# SCH_Placa-TSM-2026-II_2026-04-09.net
KiCad netlist of a schematic drawn in EasyEDA
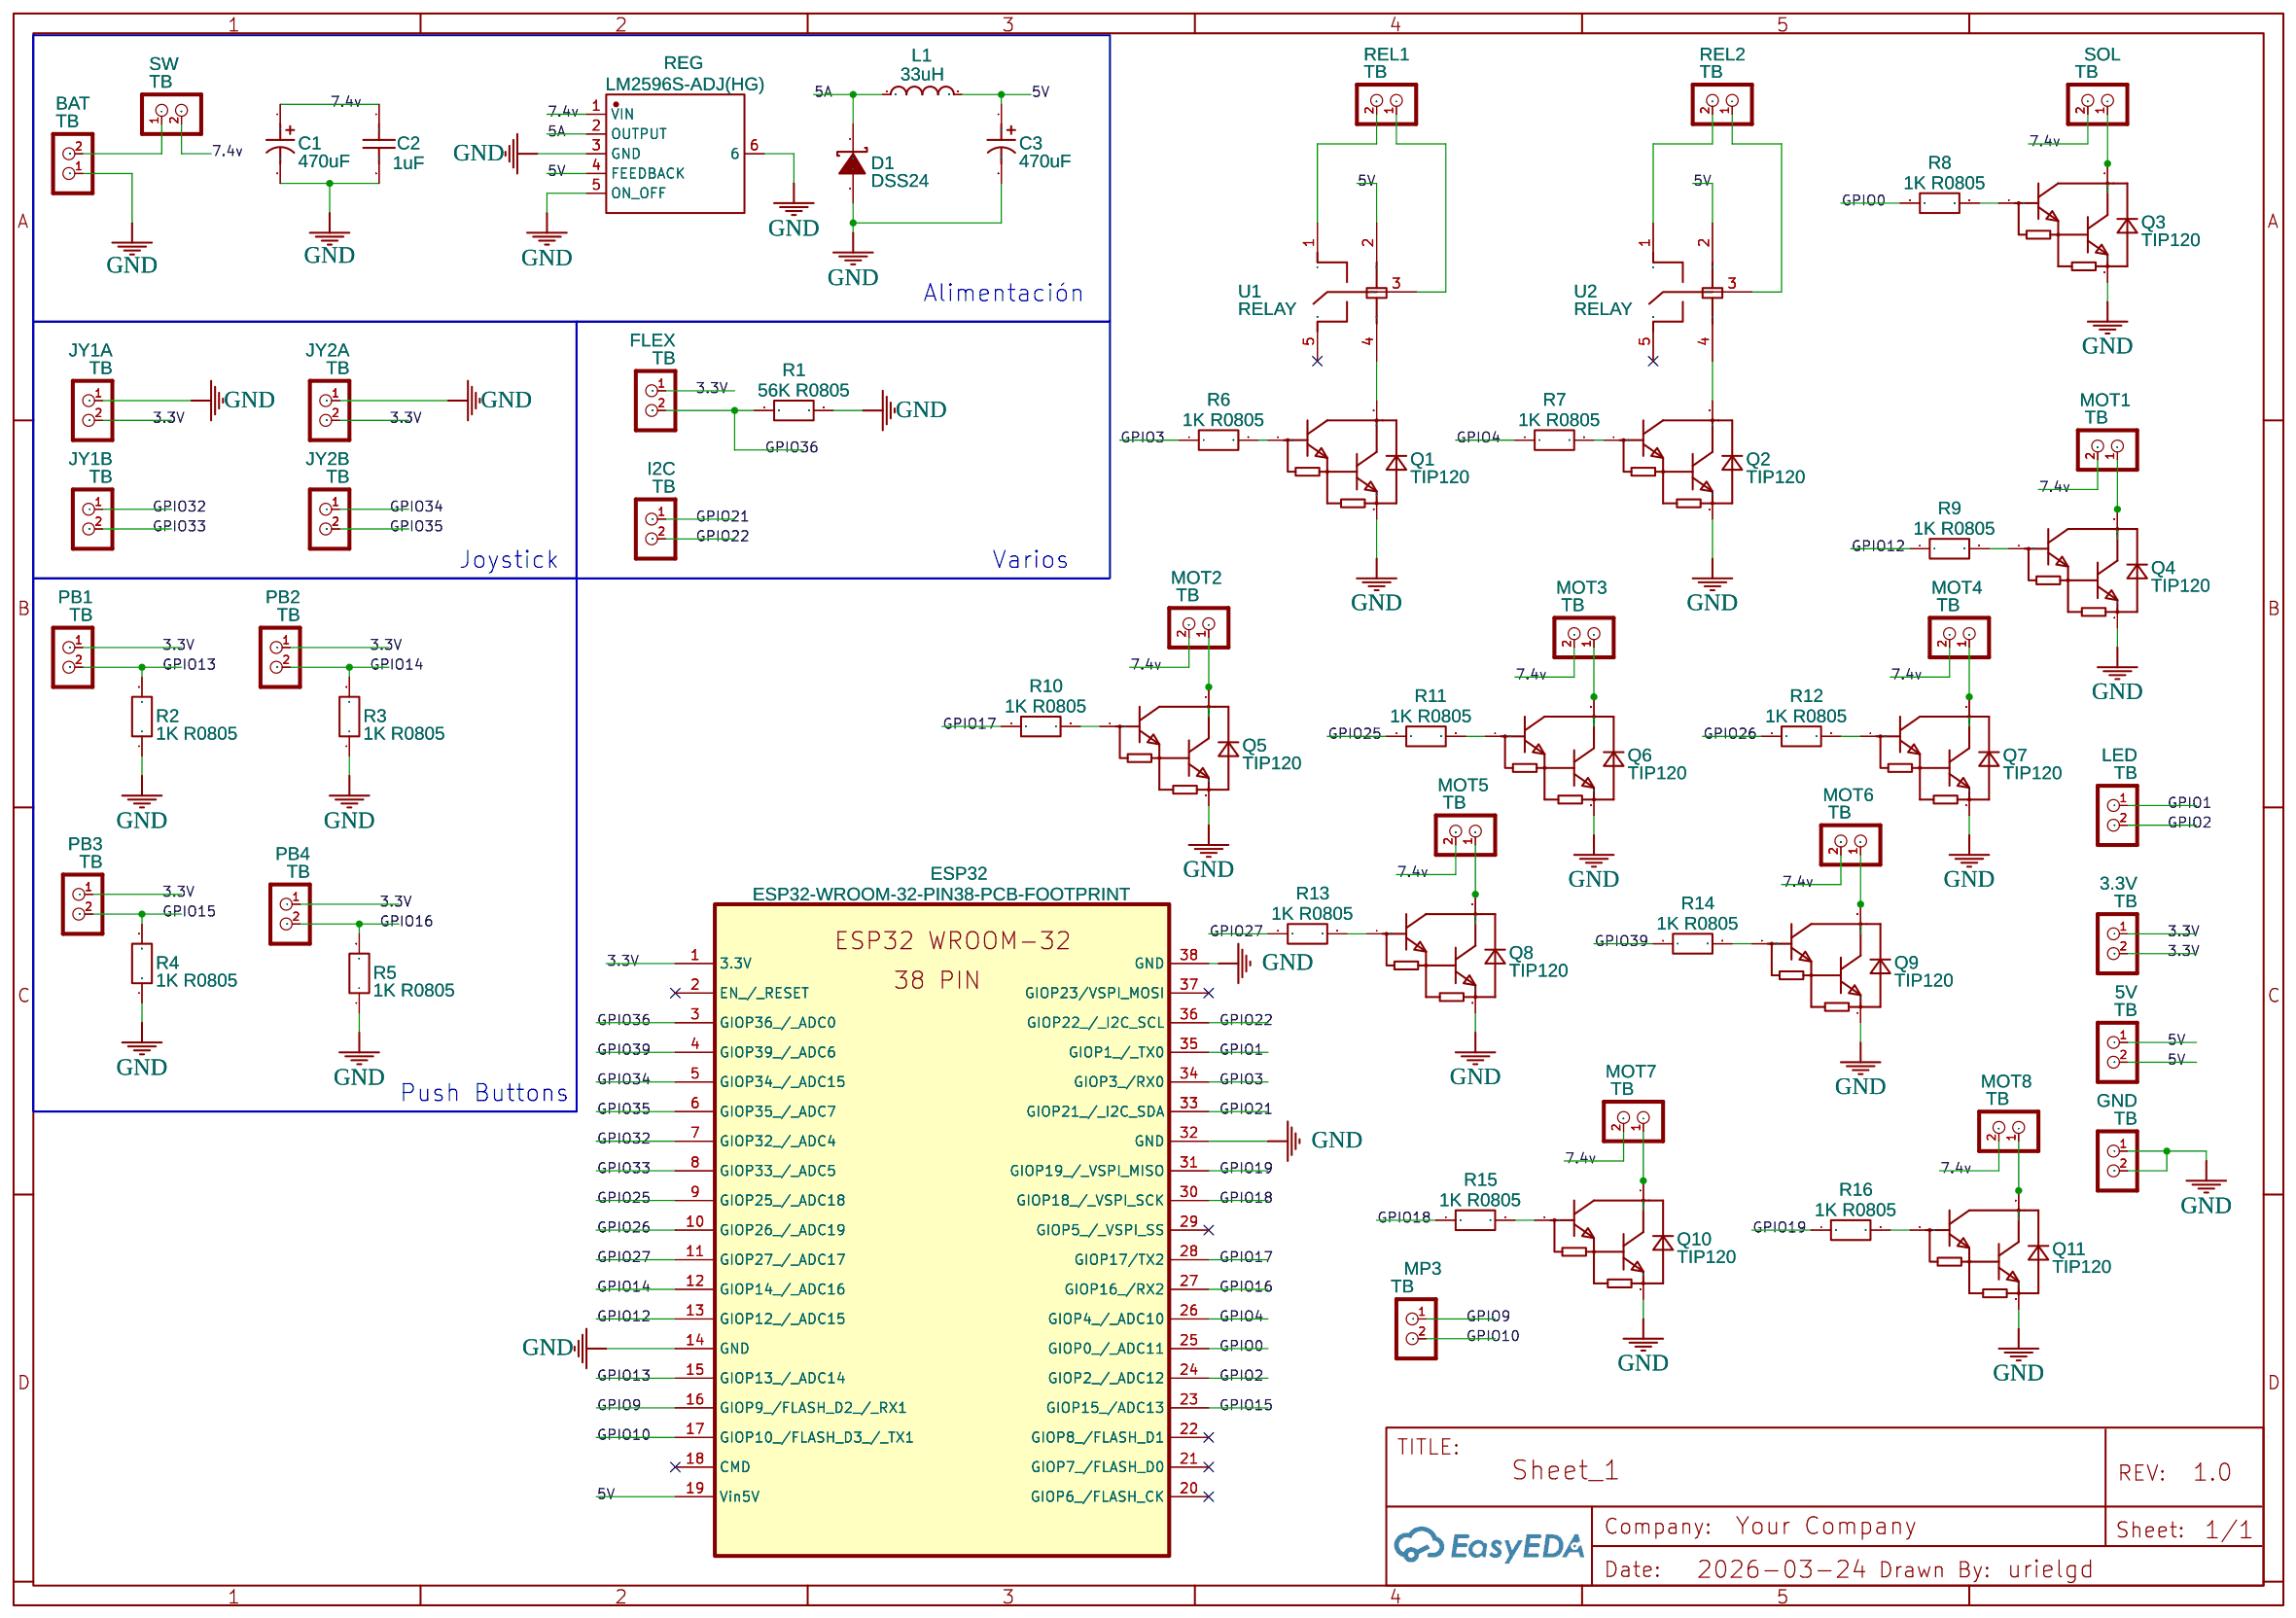
[diagram p0: schematic sheet]

(export (version "E")
  (design (tool "Eeschema 10.0.6"))
  (components
    (comp (ref "3.3V") (value "TB") (libsource (lib "") (part "TERMINAL_BLOCK_2P_5_14")))
    (comp (ref "5V") (value "TB") (libsource (lib "") (part "TERMINAL_BLOCK_2P_5_12")))
    (comp (ref "BAT") (value "TB") (libsource (lib "") (part "TERMINAL_BLOCK_2P_5_11")))
    (comp (ref "C1")
      (value "470uF")
      (fields (field (name "Manufacturer Part") "16V470uF CD288") (field (name "Manufacturer") "HRK(鸿瑞凯电子)"))
      (libsource (lib "") (part "16V470UF CD288_1"))
    )
    (comp (ref "C2")
      (value "1uF")
      (fields
        (field (name "Manufacturer Part") "TCC0805X7R105K500DTS")
        (field (name "Manufacturer") "CCTC(三环)")
      )
      (libsource (lib "") (part "TCC0805X7R105K500DTS"))
    )
    (comp (ref "C3")
      (value "470uF")
      (fields (field (name "Manufacturer Part") "16V470uF CD288") (field (name "Manufacturer") "HRK(鸿瑞凯电子)"))
      (libsource (lib "") (part "16V470UF CD288"))
    )
    (comp (ref "D1")
      (value "DSS24")
      (fields (field (name "Manufacturer") "星海"))
      (libsource (lib "") (part "DSS24"))
    )
    (comp (ref "ESP32")
      (value "ESP32-WROOM-32-PIN38-PCB-FOOTPRINT")
      (fields
        (field (name "Manufacturer Part") "ESP32-WROOM-32")
        (field (name "Manufacturer") "Espressif Systems")
      )
      (libsource (lib "") (part "ESP32-WROOM-32-PIN38-PCB-FOOTPRINT"))
    )
    (comp (ref "FLEX") (value "TB") (libsource (lib "") (part "TERMINAL_BLOCK_2P_5_10")))
    (comp (ref "GND") (value "TB") (libsource (lib "") (part "TERMINAL_BLOCK_2P_5_8")))
    (comp (ref "I2C") (value "TB") (libsource (lib "") (part "TERMINAL_BLOCK_2P_5_16")))
    (comp (ref "JY1A") (value "TB") (libsource (lib "") (part "TERMINAL_BLOCK_2P_5_3")))
    (comp (ref "JY1B") (value "TB") (libsource (lib "") (part "TERMINAL_BLOCK_2P_5_1")))
    (comp (ref "JY2A") (value "TB") (libsource (lib "") (part "TERMINAL_BLOCK_2P_5_13")))
    (comp (ref "JY2B") (value "TB") (libsource (lib "") (part "TERMINAL_BLOCK_2P_5")))
    (comp (ref "L1")
      (value "33uH")
      (fields
        (field (name "Manufacturer Part") "HPC6045CF-330M")
        (field (name "Manufacturer") "TAI-TECH(台庆)")
      )
      (libsource (lib "") (part "HPC6045CF-330M"))
    )
    (comp (ref "LED") (value "TB") (libsource (lib "") (part "TERMINAL_BLOCK_2P_5_7")))
    (comp (ref "MOT1") (value "TB") (libsource (lib "") (part "TERMINAL_BLOCK_2P_5_2")))
    (comp (ref "MOT2") (value "TB") (libsource (lib "") (part "TERMINAL_BLOCK_2P_5_2")))
    (comp (ref "MOT3") (value "TB") (libsource (lib "") (part "TERMINAL_BLOCK_2P_5_2")))
    (comp (ref "MOT4") (value "TB") (libsource (lib "") (part "TERMINAL_BLOCK_2P_5_2")))
    (comp (ref "MOT5") (value "TB") (libsource (lib "") (part "TERMINAL_BLOCK_2P_5_2")))
    (comp (ref "MOT6") (value "TB") (libsource (lib "") (part "TERMINAL_BLOCK_2P_5_2")))
    (comp (ref "MOT7") (value "TB") (libsource (lib "") (part "TERMINAL_BLOCK_2P_5_2")))
    (comp (ref "MOT8") (value "TB") (libsource (lib "") (part "TERMINAL_BLOCK_2P_5_2")))
    (comp (ref "MP3") (value "TB") (libsource (lib "") (part "TERMINAL_BLOCK_2P_5_9")))
    (comp (ref "PB1") (value "TB") (libsource (lib "") (part "TERMINAL_BLOCK_2P_5_4")))
    (comp (ref "PB2") (value "TB") (libsource (lib "") (part "TERMINAL_BLOCK_2P_5_4")))
    (comp (ref "PB3") (value "TB") (libsource (lib "") (part "TERMINAL_BLOCK_2P_5_4")))
    (comp (ref "PB4") (value "TB") (libsource (lib "") (part "TERMINAL_BLOCK_2P_5_4")))
    (comp (ref "Q1")
      (value "TIP120")
      (fields (field (name "Manufacturer") "ST(意法半导体)"))
      (libsource (lib "") (part "TIP120"))
    )
    (comp (ref "Q2")
      (value "TIP120")
      (fields (field (name "Manufacturer") "ST(意法半导体)"))
      (libsource (lib "") (part "TIP120"))
    )
    (comp (ref "Q3")
      (value "TIP120")
      (fields (field (name "Manufacturer") "ST(意法半导体)"))
      (libsource (lib "") (part "TIP120"))
    )
    (comp (ref "Q4")
      (value "TIP120")
      (fields (field (name "Manufacturer") "ST(意法半导体)"))
      (libsource (lib "") (part "TIP120"))
    )
    (comp (ref "Q5")
      (value "TIP120")
      (fields (field (name "Manufacturer") "ST(意法半导体)"))
      (libsource (lib "") (part "TIP120"))
    )
    (comp (ref "Q6")
      (value "TIP120")
      (fields (field (name "Manufacturer") "ST(意法半导体)"))
      (libsource (lib "") (part "TIP120"))
    )
    (comp (ref "Q7")
      (value "TIP120")
      (fields (field (name "Manufacturer") "ST(意法半导体)"))
      (libsource (lib "") (part "TIP120"))
    )
    (comp (ref "Q8")
      (value "TIP120")
      (fields (field (name "Manufacturer") "ST(意法半导体)"))
      (libsource (lib "") (part "TIP120"))
    )
    (comp (ref "Q9")
      (value "TIP120")
      (fields (field (name "Manufacturer") "ST(意法半导体)"))
      (libsource (lib "") (part "TIP120"))
    )
    (comp (ref "Q10")
      (value "TIP120")
      (fields (field (name "Manufacturer") "ST(意法半导体)"))
      (libsource (lib "") (part "TIP120"))
    )
    (comp (ref "Q11")
      (value "TIP120")
      (fields (field (name "Manufacturer") "ST(意法半导体)"))
      (libsource (lib "") (part "TIP120"))
    )
    (comp (ref "R1")
      (value "56K R0805")
      (fields (field (name "Manufacturer Part") "9.75K R0805"))
      (libsource (lib "") (part "9.75K R0805"))
    )
    (comp (ref "R2")
      (value "1K R0805")
      (fields (field (name "Manufacturer Part") "9.75K R0805"))
      (libsource (lib "") (part "9.75K R0805_1"))
    )
    (comp (ref "R3")
      (value "1K R0805")
      (fields (field (name "Manufacturer Part") "9.75K R0805"))
      (libsource (lib "") (part "9.75K R0805_1"))
    )
    (comp (ref "R4")
      (value "1K R0805")
      (fields (field (name "Manufacturer Part") "9.75K R0805"))
      (libsource (lib "") (part "9.75K R0805_1"))
    )
    (comp (ref "R5")
      (value "1K R0805")
      (fields (field (name "Manufacturer Part") "9.75K R0805"))
      (libsource (lib "") (part "9.75K R0805_1"))
    )
    (comp (ref "R6")
      (value "1K R0805")
      (fields (field (name "Manufacturer Part") "9.75K R0805"))
      (libsource (lib "") (part "9.75K R0805"))
    )
    (comp (ref "R7")
      (value "1K R0805")
      (fields (field (name "Manufacturer Part") "9.75K R0805"))
      (libsource (lib "") (part "9.75K R0805"))
    )
    (comp (ref "R8")
      (value "1K R0805")
      (fields (field (name "Manufacturer Part") "9.75K R0805"))
      (libsource (lib "") (part "9.75K R0805"))
    )
    (comp (ref "R9")
      (value "1K R0805")
      (fields (field (name "Manufacturer Part") "9.75K R0805"))
      (libsource (lib "") (part "9.75K R0805"))
    )
    (comp (ref "R10")
      (value "1K R0805")
      (fields (field (name "Manufacturer Part") "9.75K R0805"))
      (libsource (lib "") (part "9.75K R0805"))
    )
    (comp (ref "R11")
      (value "1K R0805")
      (fields (field (name "Manufacturer Part") "9.75K R0805"))
      (libsource (lib "") (part "9.75K R0805"))
    )
    (comp (ref "R12")
      (value "1K R0805")
      (fields (field (name "Manufacturer Part") "9.75K R0805"))
      (libsource (lib "") (part "9.75K R0805"))
    )
    (comp (ref "R13")
      (value "1K R0805")
      (fields (field (name "Manufacturer Part") "9.75K R0805"))
      (libsource (lib "") (part "9.75K R0805"))
    )
    (comp (ref "R14")
      (value "1K R0805")
      (fields (field (name "Manufacturer Part") "9.75K R0805"))
      (libsource (lib "") (part "9.75K R0805"))
    )
    (comp (ref "R15")
      (value "1K R0805")
      (fields (field (name "Manufacturer Part") "9.75K R0805"))
      (libsource (lib "") (part "9.75K R0805"))
    )
    (comp (ref "R16")
      (value "1K R0805")
      (fields (field (name "Manufacturer Part") "9.75K R0805"))
      (libsource (lib "") (part "9.75K R0805"))
    )
    (comp (ref "REG")
      (value "LM2596S-ADJ(HG)")
      (fields (field (name "Manufacturer") "HGSEMI(华冠)"))
      (libsource (lib "") (part "LM2596S-ADJ(HG)"))
    )
    (comp (ref "REL1") (value "TB") (libsource (lib "") (part "TERMINAL_BLOCK_2P_5_6")))
    (comp (ref "REL2") (value "TB") (libsource (lib "") (part "TERMINAL_BLOCK_2P_5_6")))
    (comp (ref "SOL") (value "TB") (libsource (lib "") (part "TERMINAL_BLOCK_2P_5_15")))
    (comp (ref "SW") (value "TB") (libsource (lib "") (part "TERMINAL_BLOCK_2P_5_5")))
    (comp (ref "U1")
      (value "RELAY")
      (fields (field (name "Manufacturer Part") "Relay-SPST"))
      (libsource (lib "") (part "RELAY"))
    )
    (comp (ref "U2")
      (value "RELAY")
      (fields (field (name "Manufacturer Part") "Relay-SPST"))
      (libsource (lib "") (part "RELAY"))
    )
  )
  (nets
    (net (code "1") (name "/3.3V") (class "Default")
      (node (ref "3.3V") (pin "1") (pinfunction "1_1") (pintype "unspecified"))
      (node (ref "3.3V") (pin "2") (pinfunction "2_2") (pintype "unspecified"))
      (node (ref "ESP32") (pin "1") (pinfunction "3.3V_1") (pintype "unspecified"))
      (node (ref "FLEX") (pin "1") (pinfunction "1_1") (pintype "unspecified"))
      (node (ref "JY1A") (pin "2") (pinfunction "2_2") (pintype "unspecified"))
      (node (ref "JY2A") (pin "2") (pinfunction "2_2") (pintype "unspecified"))
      (node (ref "PB1") (pin "1") (pinfunction "1_1") (pintype "unspecified"))
      (node (ref "PB2") (pin "1") (pinfunction "1_1") (pintype "unspecified"))
      (node (ref "PB3") (pin "1") (pinfunction "1_1") (pintype "unspecified"))
      (node (ref "PB4") (pin "1") (pinfunction "1_1") (pintype "unspecified"))
    )
    (net (code "2") (name "/5A") (class "Default")
      (node (ref "D1") (pin "1") (pinfunction "C_1") (pintype "unspecified"))
      (node (ref "L1") (pin "1") (pinfunction "1_1") (pintype "unspecified"))
      (node (ref "REG") (pin "2") (pinfunction "OUTPUT_2") (pintype "unspecified"))
    )
    (net (code "3") (name "/5V") (class "Default")
      (node (ref "5V") (pin "1") (pinfunction "1_1") (pintype "unspecified"))
      (node (ref "5V") (pin "2") (pinfunction "2_2") (pintype "unspecified"))
      (node (ref "C3") (pin "1") (pinfunction "1_1") (pintype "unspecified"))
      (node (ref "ESP32") (pin "19") (pinfunction "Vin5V_19") (pintype "unspecified"))
      (node (ref "L1") (pin "2") (pinfunction "2_2") (pintype "unspecified"))
      (node (ref "REG") (pin "4") (pinfunction "FEEDBACK_4") (pintype "unspecified"))
      (node (ref "U1") (pin "2") (pinfunction "2_2") (pintype "unspecified"))
      (node (ref "U2") (pin "2") (pinfunction "2_2") (pintype "unspecified"))
    )
    (net (code "4") (name "/7.4v") (class "Default")
      (node (ref "C1") (pin "1") (pinfunction "1_1") (pintype "unspecified"))
      (node (ref "C2") (pin "1") (pinfunction "1_1") (pintype "unspecified"))
      (node (ref "MOT1") (pin "2") (pinfunction "2_2") (pintype "unspecified"))
      (node (ref "MOT2") (pin "2") (pinfunction "2_2") (pintype "unspecified"))
      (node (ref "MOT3") (pin "2") (pinfunction "2_2") (pintype "unspecified"))
      (node (ref "MOT4") (pin "2") (pinfunction "2_2") (pintype "unspecified"))
      (node (ref "MOT5") (pin "2") (pinfunction "2_2") (pintype "unspecified"))
      (node (ref "MOT6") (pin "2") (pinfunction "2_2") (pintype "unspecified"))
      (node (ref "MOT7") (pin "2") (pinfunction "2_2") (pintype "unspecified"))
      (node (ref "MOT8") (pin "2") (pinfunction "2_2") (pintype "unspecified"))
      (node (ref "REG") (pin "1") (pinfunction "VIN_1") (pintype "unspecified"))
      (node (ref "SOL") (pin "2") (pinfunction "2_2") (pintype "unspecified"))
      (node (ref "SW") (pin "2") (pinfunction "2_2") (pintype "unspecified"))
    )
    (net (code "5") (name "/GPIO0") (class "Default")
      (node (ref "ESP32") (pin "25") (pinfunction "GIOP0_/_ADC11_25") (pintype "unspecified"))
      (node (ref "R8") (pin "1") (pinfunction "1_1") (pintype "unspecified"))
    )
    (net (code "6") (name "/GPIO1") (class "Default")
      (node (ref "ESP32") (pin "35") (pinfunction "GIOP1_/_TX0_35") (pintype "unspecified"))
      (node (ref "LED") (pin "1") (pinfunction "1_1") (pintype "unspecified"))
    )
    (net (code "7") (name "/GPIO2") (class "Default")
      (node (ref "ESP32") (pin "24") (pinfunction "GIOP2_/_ADC12_24") (pintype "unspecified"))
      (node (ref "LED") (pin "2") (pinfunction "2_2") (pintype "unspecified"))
    )
    (net (code "8") (name "/GPIO3") (class "Default")
      (node (ref "ESP32") (pin "34") (pinfunction "GIOP3_/RX0_34") (pintype "unspecified"))
      (node (ref "R6") (pin "1") (pinfunction "1_1") (pintype "unspecified"))
    )
    (net (code "9") (name "/GPIO4") (class "Default")
      (node (ref "ESP32") (pin "26") (pinfunction "GIOP4_/_ADC10_26") (pintype "unspecified"))
      (node (ref "R7") (pin "1") (pinfunction "1_1") (pintype "unspecified"))
    )
    (net (code "10") (name "/GPIO9") (class "Default")
      (node (ref "ESP32") (pin "16") (pinfunction "GIOP9_/FLASH_D2_/_RX1_16") (pintype "unspecified"))
      (node (ref "MP3") (pin "1") (pinfunction "1_1") (pintype "unspecified"))
    )
    (net (code "11") (name "/GPIO10") (class "Default")
      (node (ref "ESP32") (pin "17") (pinfunction "GIOP10_/FLASH_D3_/_TX1_17") (pintype "unspecified"))
      (node (ref "MP3") (pin "2") (pinfunction "2_2") (pintype "unspecified"))
    )
    (net (code "12") (name "/GPIO12") (class "Default")
      (node (ref "ESP32") (pin "13") (pinfunction "GIOP12_/_ADC15_13") (pintype "unspecified"))
      (node (ref "R9") (pin "1") (pinfunction "1_1") (pintype "unspecified"))
    )
    (net (code "13") (name "/GPIO13") (class "Default")
      (node (ref "ESP32") (pin "15") (pinfunction "GIOP13_/_ADC14_15") (pintype "unspecified"))
      (node (ref "PB1") (pin "2") (pinfunction "2_2") (pintype "unspecified"))
      (node (ref "R2") (pin "2") (pinfunction "2_2") (pintype "unspecified"))
    )
    (net (code "14") (name "/GPIO14") (class "Default")
      (node (ref "ESP32") (pin "12") (pinfunction "GIOP14_/_ADC16_12") (pintype "unspecified"))
      (node (ref "PB2") (pin "2") (pinfunction "2_2") (pintype "unspecified"))
      (node (ref "R3") (pin "2") (pinfunction "2_2") (pintype "unspecified"))
    )
    (net (code "15") (name "/GPIO15") (class "Default")
      (node (ref "ESP32") (pin "23") (pinfunction "GIOP15_/ADC13_23") (pintype "unspecified"))
      (node (ref "PB3") (pin "2") (pinfunction "2_2") (pintype "unspecified"))
      (node (ref "R4") (pin "2") (pinfunction "2_2") (pintype "unspecified"))
    )
    (net (code "16") (name "/GPIO16") (class "Default")
      (node (ref "ESP32") (pin "27") (pinfunction "GIOP16_/RX2_27") (pintype "unspecified"))
      (node (ref "PB4") (pin "2") (pinfunction "2_2") (pintype "unspecified"))
      (node (ref "R5") (pin "2") (pinfunction "2_2") (pintype "unspecified"))
    )
    (net (code "17") (name "/GPIO17") (class "Default")
      (node (ref "ESP32") (pin "28") (pinfunction "GIOP17/TX2_28") (pintype "unspecified"))
      (node (ref "R10") (pin "1") (pinfunction "1_1") (pintype "unspecified"))
    )
    (net (code "18") (name "/GPIO18") (class "Default")
      (node (ref "ESP32") (pin "30") (pinfunction "GIOP18_/_VSPI_SCK_30") (pintype "unspecified"))
      (node (ref "R15") (pin "1") (pinfunction "1_1") (pintype "unspecified"))
    )
    (net (code "19") (name "/GPIO19") (class "Default")
      (node (ref "ESP32") (pin "31") (pinfunction "GIOP19_/_VSPI_MISO_31") (pintype "unspecified"))
      (node (ref "R16") (pin "1") (pinfunction "1_1") (pintype "unspecified"))
    )
    (net (code "20") (name "/GPIO21") (class "Default")
      (node (ref "ESP32") (pin "33") (pinfunction "GIOP21_/_I2C_SDA_33") (pintype "unspecified"))
      (node (ref "I2C") (pin "1") (pinfunction "1_1") (pintype "unspecified"))
    )
    (net (code "21") (name "/GPIO22") (class "Default")
      (node (ref "ESP32") (pin "36") (pinfunction "GIOP22_/_I2C_SCL_36") (pintype "unspecified"))
      (node (ref "I2C") (pin "2") (pinfunction "2_2") (pintype "unspecified"))
    )
    (net (code "22") (name "/GPIO25") (class "Default")
      (node (ref "ESP32") (pin "9") (pinfunction "GIOP25_/_ADC18_9") (pintype "unspecified"))
      (node (ref "R11") (pin "1") (pinfunction "1_1") (pintype "unspecified"))
    )
    (net (code "23") (name "/GPIO26") (class "Default")
      (node (ref "ESP32") (pin "10") (pinfunction "GIOP26_/_ADC19_10") (pintype "unspecified"))
      (node (ref "R12") (pin "1") (pinfunction "1_1") (pintype "unspecified"))
    )
    (net (code "24") (name "/GPIO27") (class "Default")
      (node (ref "ESP32") (pin "11") (pinfunction "GIOP27_/_ADC17_11") (pintype "unspecified"))
      (node (ref "R13") (pin "1") (pinfunction "1_1") (pintype "unspecified"))
    )
    (net (code "25") (name "/GPIO32") (class "Default")
      (node (ref "ESP32") (pin "7") (pinfunction "GIOP32_/_ADC4_7") (pintype "unspecified"))
      (node (ref "JY1B") (pin "1") (pinfunction "1_1") (pintype "unspecified"))
    )
    (net (code "26") (name "/GPIO33") (class "Default")
      (node (ref "ESP32") (pin "8") (pinfunction "GIOP33_/_ADC5_8") (pintype "unspecified"))
      (node (ref "JY1B") (pin "2") (pinfunction "2_2") (pintype "unspecified"))
    )
    (net (code "27") (name "/GPIO34") (class "Default")
      (node (ref "ESP32") (pin "5") (pinfunction "GIOP34_/_ADC15_5") (pintype "unspecified"))
      (node (ref "JY2B") (pin "1") (pinfunction "1_1") (pintype "unspecified"))
    )
    (net (code "28") (name "/GPIO35") (class "Default")
      (node (ref "ESP32") (pin "6") (pinfunction "GIOP35_/_ADC7_6") (pintype "unspecified"))
      (node (ref "JY2B") (pin "2") (pinfunction "2_2") (pintype "unspecified"))
    )
    (net (code "29") (name "/GPIO36") (class "Default")
      (node (ref "ESP32") (pin "3") (pinfunction "GIOP36_/_ADC0_3") (pintype "unspecified"))
      (node (ref "FLEX") (pin "2") (pinfunction "2_2") (pintype "unspecified"))
      (node (ref "R1") (pin "1") (pinfunction "1_1") (pintype "unspecified"))
    )
    (net (code "30") (name "/GPIO39") (class "Default")
      (node (ref "ESP32") (pin "4") (pinfunction "GIOP39_/_ADC6_4") (pintype "unspecified"))
      (node (ref "R14") (pin "1") (pinfunction "1_1") (pintype "unspecified"))
    )
    (net (code "31") (name "GND") (class "Default")
      (node (ref "BAT") (pin "1") (pinfunction "1_1") (pintype "unspecified"))
      (node (ref "C1") (pin "2") (pinfunction "2_2") (pintype "unspecified"))
      (node (ref "C2") (pin "2") (pinfunction "2_2") (pintype "unspecified"))
      (node (ref "C3") (pin "2") (pinfunction "2_2") (pintype "unspecified"))
      (node (ref "D1") (pin "2") (pinfunction "A_2") (pintype "unspecified"))
      (node (ref "ESP32") (pin "14") (pinfunction "GND_14") (pintype "unspecified"))
      (node (ref "ESP32") (pin "32") (pinfunction "GND_32") (pintype "unspecified"))
      (node (ref "ESP32") (pin "38") (pinfunction "GND_38") (pintype "unspecified"))
      (node (ref "GND") (pin "1") (pinfunction "1_1") (pintype "unspecified"))
      (node (ref "GND") (pin "2") (pinfunction "2_2") (pintype "unspecified"))
      (node (ref "JY1A") (pin "1") (pinfunction "1_1") (pintype "unspecified"))
      (node (ref "JY2A") (pin "1") (pinfunction "1_1") (pintype "unspecified"))
      (node (ref "Q1") (pin "3") (pinfunction "E_3") (pintype "input"))
      (node (ref "Q10") (pin "3") (pinfunction "E_3") (pintype "input"))
      (node (ref "Q11") (pin "3") (pinfunction "E_3") (pintype "input"))
      (node (ref "Q2") (pin "3") (pinfunction "E_3") (pintype "input"))
      (node (ref "Q3") (pin "3") (pinfunction "E_3") (pintype "input"))
      (node (ref "Q4") (pin "3") (pinfunction "E_3") (pintype "input"))
      (node (ref "Q5") (pin "3") (pinfunction "E_3") (pintype "input"))
      (node (ref "Q6") (pin "3") (pinfunction "E_3") (pintype "input"))
      (node (ref "Q7") (pin "3") (pinfunction "E_3") (pintype "input"))
      (node (ref "Q8") (pin "3") (pinfunction "E_3") (pintype "input"))
      (node (ref "Q9") (pin "3") (pinfunction "E_3") (pintype "input"))
      (node (ref "R1") (pin "2") (pinfunction "2_2") (pintype "unspecified"))
      (node (ref "R2") (pin "1") (pinfunction "1_1") (pintype "unspecified"))
      (node (ref "R3") (pin "1") (pinfunction "1_1") (pintype "unspecified"))
      (node (ref "R4") (pin "1") (pinfunction "1_1") (pintype "unspecified"))
      (node (ref "R5") (pin "1") (pinfunction "1_1") (pintype "unspecified"))
      (node (ref "REG") (pin "3") (pinfunction "GND_3") (pintype "unspecified"))
      (node (ref "REG") (pin "5") (pinfunction "ON_OFF_5") (pintype "unspecified"))
      (node (ref "REG") (pin "6") (pinfunction "6_6") (pintype "unspecified"))
    )
    (net (code "32") (name "Net-(BAT-Pad2)") (class "Default")
      (node (ref "BAT") (pin "2") (pinfunction "2_2") (pintype "unspecified"))
      (node (ref "SW") (pin "1") (pinfunction "1_1") (pintype "unspecified"))
    )
    (net (code "33") (name "Net-(Q1-B)") (class "Default")
      (node (ref "Q1") (pin "1") (pinfunction "B_1") (pintype "input"))
      (node (ref "R6") (pin "2") (pinfunction "2_2") (pintype "unspecified"))
    )
    (net (code "34") (name "Net-(Q1-C)") (class "Default")
      (node (ref "Q1") (pin "2") (pinfunction "C_2") (pintype "input"))
      (node (ref "U1") (pin "4") (pinfunction "4_4") (pintype "unspecified"))
    )
    (net (code "35") (name "Net-(Q2-B)") (class "Default")
      (node (ref "Q2") (pin "1") (pinfunction "B_1") (pintype "input"))
      (node (ref "R7") (pin "2") (pinfunction "2_2") (pintype "unspecified"))
    )
    (net (code "36") (name "Net-(Q2-C)") (class "Default")
      (node (ref "Q2") (pin "2") (pinfunction "C_2") (pintype "input"))
      (node (ref "U2") (pin "4") (pinfunction "4_4") (pintype "unspecified"))
    )
    (net (code "37") (name "Net-(Q3-B)") (class "Default")
      (node (ref "Q3") (pin "1") (pinfunction "B_1") (pintype "input"))
      (node (ref "R8") (pin "2") (pinfunction "2_2") (pintype "unspecified"))
    )
    (net (code "38") (name "Net-(Q3-C)") (class "Default")
      (node (ref "Q3") (pin "2") (pinfunction "C_2") (pintype "input"))
      (node (ref "SOL") (pin "1") (pinfunction "1_1") (pintype "unspecified"))
    )
    (net (code "39") (name "Net-(Q4-B)") (class "Default")
      (node (ref "Q4") (pin "1") (pinfunction "B_1") (pintype "input"))
      (node (ref "R9") (pin "2") (pinfunction "2_2") (pintype "unspecified"))
    )
    (net (code "40") (name "Net-(Q4-C)") (class "Default")
      (node (ref "MOT1") (pin "1") (pinfunction "1_1") (pintype "unspecified"))
      (node (ref "Q4") (pin "2") (pinfunction "C_2") (pintype "input"))
    )
    (net (code "41") (name "Net-(Q5-B)") (class "Default")
      (node (ref "Q5") (pin "1") (pinfunction "B_1") (pintype "input"))
      (node (ref "R10") (pin "2") (pinfunction "2_2") (pintype "unspecified"))
    )
    (net (code "42") (name "Net-(Q5-C)") (class "Default")
      (node (ref "MOT2") (pin "1") (pinfunction "1_1") (pintype "unspecified"))
      (node (ref "Q5") (pin "2") (pinfunction "C_2") (pintype "input"))
    )
    (net (code "43") (name "Net-(Q6-B)") (class "Default")
      (node (ref "Q6") (pin "1") (pinfunction "B_1") (pintype "input"))
      (node (ref "R11") (pin "2") (pinfunction "2_2") (pintype "unspecified"))
    )
    (net (code "44") (name "Net-(Q6-C)") (class "Default")
      (node (ref "MOT3") (pin "1") (pinfunction "1_1") (pintype "unspecified"))
      (node (ref "Q6") (pin "2") (pinfunction "C_2") (pintype "input"))
    )
    (net (code "45") (name "Net-(Q7-B)") (class "Default")
      (node (ref "Q7") (pin "1") (pinfunction "B_1") (pintype "input"))
      (node (ref "R12") (pin "2") (pinfunction "2_2") (pintype "unspecified"))
    )
    (net (code "46") (name "Net-(Q7-C)") (class "Default")
      (node (ref "MOT4") (pin "1") (pinfunction "1_1") (pintype "unspecified"))
      (node (ref "Q7") (pin "2") (pinfunction "C_2") (pintype "input"))
    )
    (net (code "47") (name "Net-(Q8-B)") (class "Default")
      (node (ref "Q8") (pin "1") (pinfunction "B_1") (pintype "input"))
      (node (ref "R13") (pin "2") (pinfunction "2_2") (pintype "unspecified"))
    )
    (net (code "48") (name "Net-(Q8-C)") (class "Default")
      (node (ref "MOT5") (pin "1") (pinfunction "1_1") (pintype "unspecified"))
      (node (ref "Q8") (pin "2") (pinfunction "C_2") (pintype "input"))
    )
    (net (code "49") (name "Net-(Q9-B)") (class "Default")
      (node (ref "Q9") (pin "1") (pinfunction "B_1") (pintype "input"))
      (node (ref "R14") (pin "2") (pinfunction "2_2") (pintype "unspecified"))
    )
    (net (code "50") (name "Net-(Q9-C)") (class "Default")
      (node (ref "MOT6") (pin "1") (pinfunction "1_1") (pintype "unspecified"))
      (node (ref "Q9") (pin "2") (pinfunction "C_2") (pintype "input"))
    )
    (net (code "51") (name "Net-(Q10-B)") (class "Default")
      (node (ref "Q10") (pin "1") (pinfunction "B_1") (pintype "input"))
      (node (ref "R15") (pin "2") (pinfunction "2_2") (pintype "unspecified"))
    )
    (net (code "52") (name "Net-(Q10-C)") (class "Default")
      (node (ref "MOT7") (pin "1") (pinfunction "1_1") (pintype "unspecified"))
      (node (ref "Q10") (pin "2") (pinfunction "C_2") (pintype "input"))
    )
    (net (code "53") (name "Net-(Q11-B)") (class "Default")
      (node (ref "Q11") (pin "1") (pinfunction "B_1") (pintype "input"))
      (node (ref "R16") (pin "2") (pinfunction "2_2") (pintype "unspecified"))
    )
    (net (code "54") (name "Net-(Q11-C)") (class "Default")
      (node (ref "MOT8") (pin "1") (pinfunction "1_1") (pintype "unspecified"))
      (node (ref "Q11") (pin "2") (pinfunction "C_2") (pintype "input"))
    )
    (net (code "55") (name "Net-(REL1-Pad1)") (class "Default")
      (node (ref "REL1") (pin "1") (pinfunction "1_1") (pintype "unspecified"))
      (node (ref "U1") (pin "3") (pinfunction "3_3") (pintype "unspecified"))
    )
    (net (code "56") (name "Net-(REL1-Pad2)") (class "Default")
      (node (ref "REL1") (pin "2") (pinfunction "2_2") (pintype "unspecified"))
      (node (ref "U1") (pin "1") (pinfunction "1_1") (pintype "unspecified"))
    )
    (net (code "57") (name "Net-(REL2-Pad1)") (class "Default")
      (node (ref "REL2") (pin "1") (pinfunction "1_1") (pintype "unspecified"))
      (node (ref "U2") (pin "3") (pinfunction "3_3") (pintype "unspecified"))
    )
    (net (code "58") (name "Net-(REL2-Pad2)") (class "Default")
      (node (ref "REL2") (pin "2") (pinfunction "2_2") (pintype "unspecified"))
      (node (ref "U2") (pin "1") (pinfunction "1_1") (pintype "unspecified"))
    )
    (net (code "59") (name "unconnected-(ESP32-CMD-Pad18)") (class "Default")
      (node (ref "ESP32") (pin "18") (pinfunction "CMD_18") (pintype "unspecified+no_connect"))
    )
    (net (code "60") (name "unconnected-(ESP32-EN_{slash}_RESET-Pad2)") (class "Default")
      (node (ref "ESP32") (pin "2") (pinfunction "EN_/_RESET_2") (pintype "unspecified+no_connect"))
    )
    (net (code "61") (name "unconnected-(ESP32-GIOP5_{slash}_VSPI_SS-Pad29)") (class "Default")
      (node (ref "ESP32") (pin "29") (pinfunction "GIOP5_/_VSPI_SS_29") (pintype "unspecified+no_connect"))
    )
    (net (code "62") (name "unconnected-(ESP32-GIOP6_{slash}FLASH_CK-Pad20)") (class "Default")
      (node (ref "ESP32") (pin "20") (pinfunction "GIOP6_/FLASH_CK_20") (pintype "unspecified+no_connect"))
    )
    (net (code "63") (name "unconnected-(ESP32-GIOP7_{slash}FLASH_D0-Pad21)") (class "Default")
      (node (ref "ESP32") (pin "21") (pinfunction "GIOP7_/FLASH_D0_21") (pintype "unspecified+no_connect"))
    )
    (net (code "64") (name "unconnected-(ESP32-GIOP8_{slash}FLASH_D1-Pad22)") (class "Default")
      (node (ref "ESP32") (pin "22") (pinfunction "GIOP8_/FLASH_D1_22") (pintype "unspecified+no_connect"))
    )
    (net (code "65") (name "unconnected-(ESP32-GIOP23{slash}VSPI_MOSI-Pad37)") (class "Default")
      (node (ref "ESP32") (pin "37") (pinfunction "GIOP23/VSPI_MOSI_37") (pintype "unspecified+no_connect"))
    )
    (net (code "66") (name "unconnected-(U1-Pad5)") (class "Default")
      (node (ref "U1") (pin "5") (pinfunction "5_5") (pintype "unspecified+no_connect"))
    )
    (net (code "67") (name "unconnected-(U2-Pad5)") (class "Default")
      (node (ref "U2") (pin "5") (pinfunction "5_5") (pintype "unspecified+no_connect"))
    )
  )
)
